# GOLpHAT.net
KiCad netlist of a schematic drawn in EAGLE
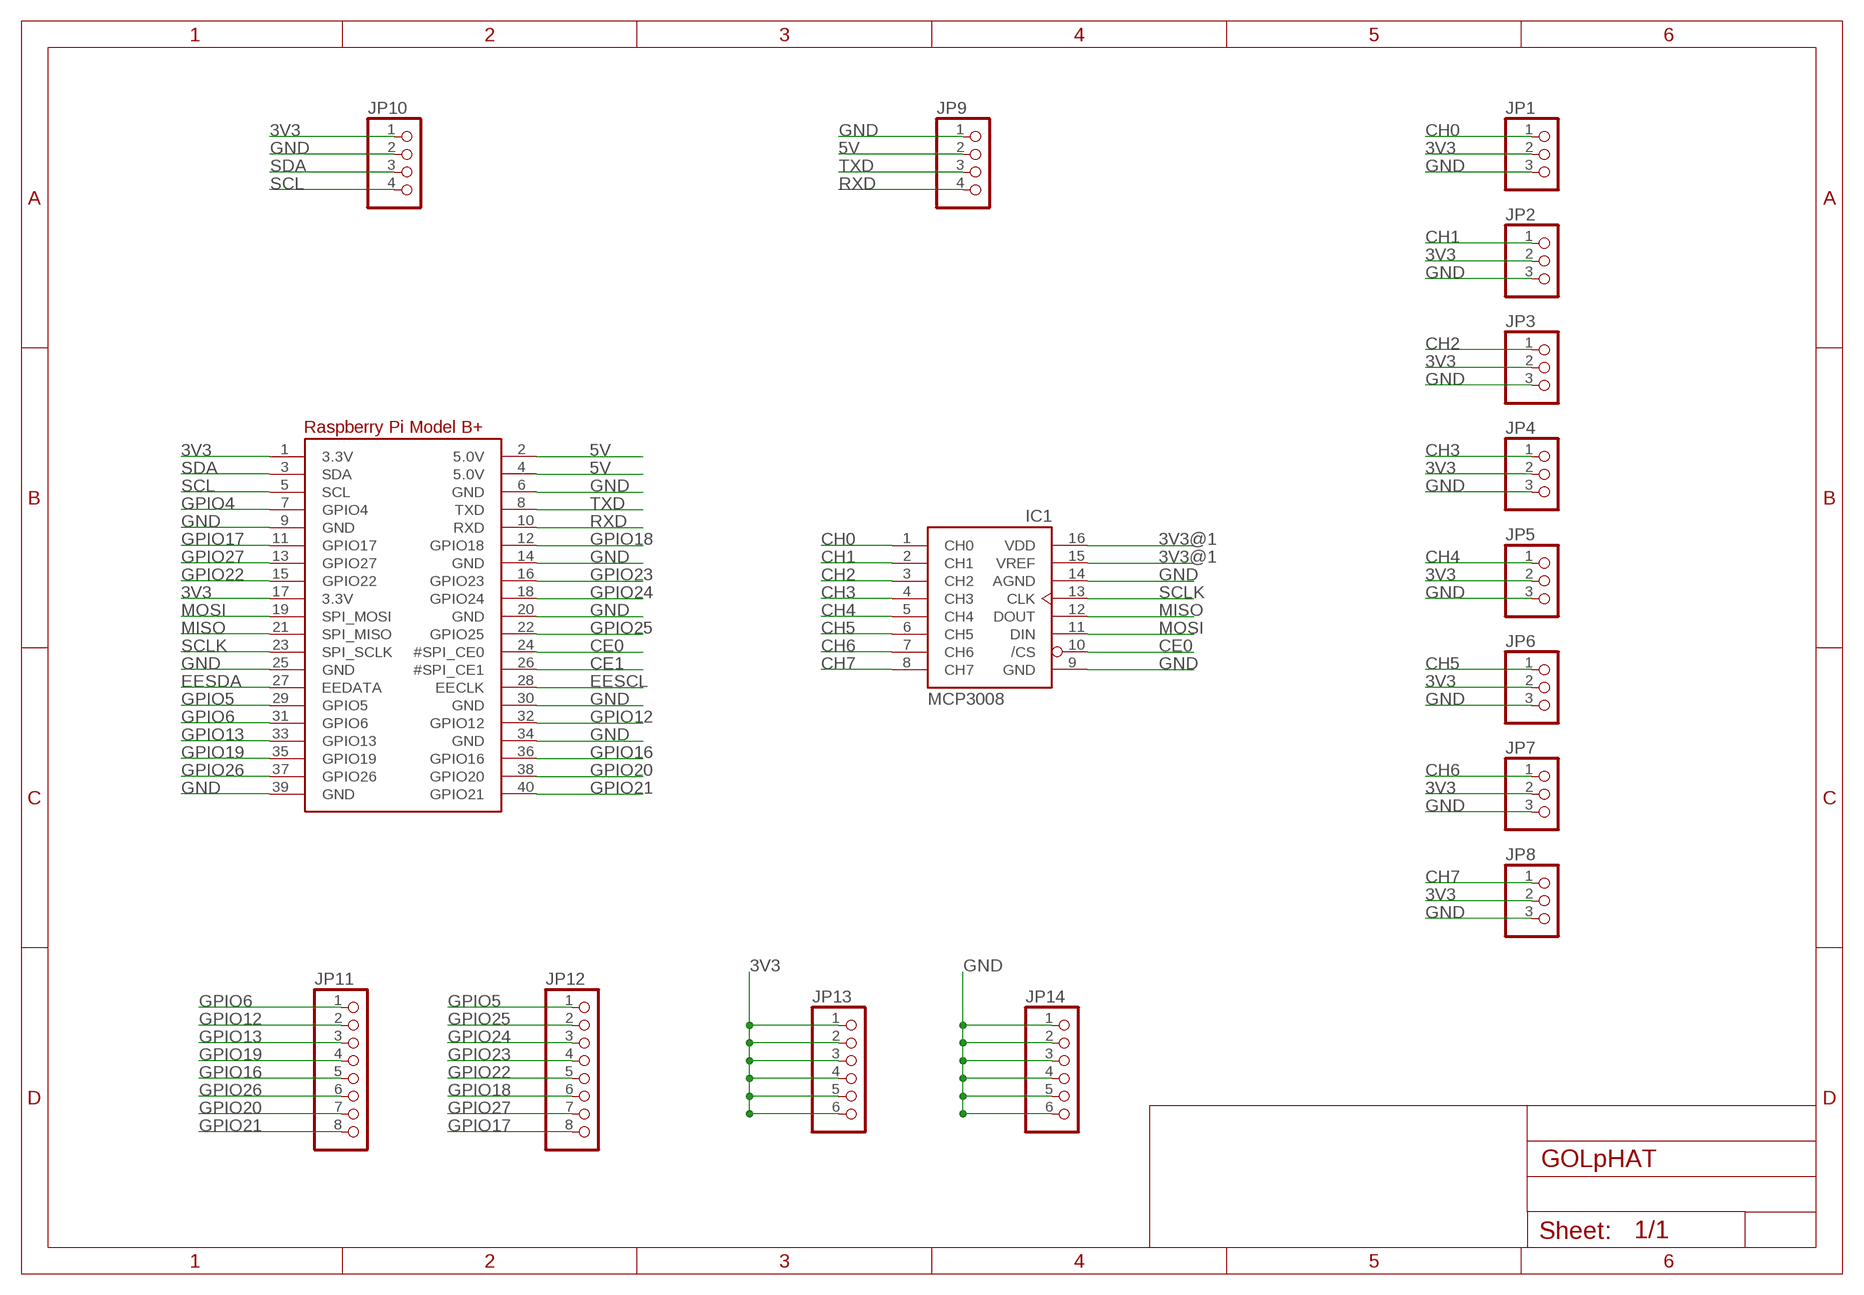
[diagram p0: schematic, sheet 1]

(export (version "E")
  (design (tool "Eeschema 10.0.6"))
  (components
    (comp (ref "IC1")
      (value "MCP3008")
      (footprint "eagle-import:DIL16")
      (libsource (lib "eagle-import") (part "MCP3008"))
    )
    (comp (ref "JP1")
      (value "PINHD-1X3")
      (footprint "eagle-import:1X03")
      (libsource (lib "eagle-import") (part "PINHD-1X3"))
    )
    (comp (ref "JP2")
      (value "PINHD-1X3")
      (footprint "eagle-import:1X03")
      (libsource (lib "eagle-import") (part "PINHD-1X3"))
    )
    (comp (ref "JP3")
      (value "PINHD-1X3")
      (footprint "eagle-import:1X03")
      (libsource (lib "eagle-import") (part "PINHD-1X3"))
    )
    (comp (ref "JP4")
      (value "PINHD-1X3")
      (footprint "eagle-import:1X03")
      (libsource (lib "eagle-import") (part "PINHD-1X3"))
    )
    (comp (ref "JP5")
      (value "PINHD-1X3")
      (footprint "eagle-import:1X03")
      (libsource (lib "eagle-import") (part "PINHD-1X3"))
    )
    (comp (ref "JP6")
      (value "PINHD-1X3")
      (footprint "eagle-import:1X03")
      (libsource (lib "eagle-import") (part "PINHD-1X3"))
    )
    (comp (ref "JP7")
      (value "PINHD-1X3")
      (footprint "eagle-import:1X03")
      (libsource (lib "eagle-import") (part "PINHD-1X3"))
    )
    (comp (ref "JP8")
      (value "PINHD-1X3")
      (footprint "eagle-import:1X03")
      (libsource (lib "eagle-import") (part "PINHD-1X3"))
    )
    (comp (ref "JP9")
      (value "PINHD-1X4")
      (footprint "eagle-import:1X04")
      (libsource (lib "eagle-import") (part "PINHD-1X4"))
    )
    (comp (ref "JP10")
      (value "PINHD-1X4")
      (footprint "eagle-import:1X04")
      (libsource (lib "eagle-import") (part "PINHD-1X4"))
    )
    (comp (ref "JP11")
      (value "PINHD-1X8CLEANBIG")
      (footprint "eagle-import:1X08-CLEANBIG")
      (libsource (lib "eagle-import") (part "PINHD-1X8CLEANBIG"))
    )
    (comp (ref "JP12")
      (value "PINHD-1X8CLEANBIG")
      (footprint "eagle-import:1X08-CLEANBIG")
      (libsource (lib "eagle-import") (part "PINHD-1X8CLEANBIG"))
    )
    (comp (ref "JP13")
      (value "PINHD-1X6CB")
      (footprint "eagle-import:1X06-CLEANBIG")
      (libsource (lib "eagle-import") (part "PINHD-1X6CB"))
    )
    (comp (ref "JP14")
      (value "PINHD-1X6CB")
      (footprint "eagle-import:1X06-CLEANBIG")
      (libsource (lib "eagle-import") (part "PINHD-1X6CB"))
    )
    (comp (ref "RPI1")
      (value "RASPBERRYPI_BPLUS_PHAT")
      (footprint "eagle-import:PI_BONNET")
      (libsource (lib "eagle-import") (part "RASPBERRYPI_BPLUS_PHAT"))
    )
  )
  (nets
    (net (code "1") (name "/3V3") (class "Default")
      (node (ref "JP1") (pin "2") (pinfunction "2_2") (pintype "passive"))
      (node (ref "JP10") (pin "1") (pinfunction "1_1") (pintype "passive"))
      (node (ref "JP13") (pin "1") (pinfunction "1_1") (pintype "passive"))
      (node (ref "JP13") (pin "2") (pinfunction "2_2") (pintype "passive"))
      (node (ref "JP13") (pin "3") (pinfunction "3_3") (pintype "passive"))
      (node (ref "JP13") (pin "4") (pinfunction "4_4") (pintype "passive"))
      (node (ref "JP13") (pin "5") (pinfunction "5_5") (pintype "passive"))
      (node (ref "JP13") (pin "6") (pinfunction "6_6") (pintype "passive"))
      (node (ref "JP2") (pin "2") (pinfunction "2_2") (pintype "passive"))
      (node (ref "JP3") (pin "2") (pinfunction "2_2") (pintype "passive"))
      (node (ref "JP4") (pin "2") (pinfunction "2_2") (pintype "passive"))
      (node (ref "JP5") (pin "2") (pinfunction "2_2") (pintype "passive"))
      (node (ref "JP6") (pin "2") (pinfunction "2_2") (pintype "passive"))
      (node (ref "JP7") (pin "2") (pinfunction "2_2") (pintype "passive"))
      (node (ref "JP8") (pin "2") (pinfunction "2_2") (pintype "passive"))
      (node (ref "RPI1") (pin "1") (pinfunction "3.3V_1") (pintype "power_in"))
      (node (ref "RPI1") (pin "17") (pinfunction "3.3V_17") (pintype "power_in"))
    )
    (net (code "2") (name "/3V3@1") (class "Default")
      (node (ref "IC1") (pin "15") (pinfunction "VREF_15") (pintype "input"))
      (node (ref "IC1") (pin "16") (pinfunction "VDD_16") (pintype "power_in"))
    )
    (net (code "3") (name "/5V") (class "Default")
      (node (ref "JP9") (pin "2") (pinfunction "2_2") (pintype "passive"))
      (node (ref "RPI1") (pin "2") (pinfunction "5.0V_2") (pintype "power_in"))
      (node (ref "RPI1") (pin "4") (pinfunction "5.0V_4") (pintype "power_in"))
    )
    (net (code "4") (name "/CE0") (class "Default")
      (node (ref "IC1") (pin "10") (pinfunction "/CS_10") (pintype "input"))
      (node (ref "RPI1") (pin "24") (pinfunction "#SPI_CE0_24") (pintype "bidirectional"))
    )
    (net (code "5") (name "/CE1") (class "Default")
      (node (ref "RPI1") (pin "26") (pinfunction "#SPI_CE1_26") (pintype "bidirectional"))
    )
    (net (code "6") (name "/CH0") (class "Default")
      (node (ref "IC1") (pin "1") (pinfunction "CH0_1") (pintype "input"))
      (node (ref "JP1") (pin "1") (pinfunction "1_1") (pintype "passive"))
    )
    (net (code "7") (name "/CH1") (class "Default")
      (node (ref "IC1") (pin "2") (pinfunction "CH1_2") (pintype "input"))
      (node (ref "JP2") (pin "1") (pinfunction "1_1") (pintype "passive"))
    )
    (net (code "8") (name "/CH2") (class "Default")
      (node (ref "IC1") (pin "3") (pinfunction "CH2_3") (pintype "input"))
      (node (ref "JP3") (pin "1") (pinfunction "1_1") (pintype "passive"))
    )
    (net (code "9") (name "/CH3") (class "Default")
      (node (ref "IC1") (pin "4") (pinfunction "CH3_4") (pintype "input"))
      (node (ref "JP4") (pin "1") (pinfunction "1_1") (pintype "passive"))
    )
    (net (code "10") (name "/CH4") (class "Default")
      (node (ref "IC1") (pin "5") (pinfunction "CH4_5") (pintype "input"))
      (node (ref "JP5") (pin "1") (pinfunction "1_1") (pintype "passive"))
    )
    (net (code "11") (name "/CH5") (class "Default")
      (node (ref "IC1") (pin "6") (pinfunction "CH5_6") (pintype "input"))
      (node (ref "JP6") (pin "1") (pinfunction "1_1") (pintype "passive"))
    )
    (net (code "12") (name "/CH6") (class "Default")
      (node (ref "IC1") (pin "7") (pinfunction "CH6_7") (pintype "input"))
      (node (ref "JP7") (pin "1") (pinfunction "1_1") (pintype "passive"))
    )
    (net (code "13") (name "/CH7") (class "Default")
      (node (ref "IC1") (pin "8") (pinfunction "CH7_8") (pintype "input"))
      (node (ref "JP8") (pin "1") (pinfunction "1_1") (pintype "passive"))
    )
    (net (code "14") (name "/EESCL") (class "Default")
      (node (ref "RPI1") (pin "28") (pinfunction "EECLK_28") (pintype "bidirectional"))
    )
    (net (code "15") (name "/EESDA") (class "Default")
      (node (ref "RPI1") (pin "27") (pinfunction "EEDATA_27") (pintype "bidirectional"))
    )
    (net (code "16") (name "/GND") (class "Default")
      (node (ref "IC1") (pin "14") (pinfunction "AGND_14") (pintype "power_in"))
      (node (ref "IC1") (pin "9") (pinfunction "GND_9") (pintype "power_in"))
      (node (ref "JP1") (pin "3") (pinfunction "3_3") (pintype "passive"))
      (node (ref "JP10") (pin "2") (pinfunction "2_2") (pintype "passive"))
      (node (ref "JP14") (pin "1") (pinfunction "1_1") (pintype "passive"))
      (node (ref "JP14") (pin "2") (pinfunction "2_2") (pintype "passive"))
      (node (ref "JP14") (pin "3") (pinfunction "3_3") (pintype "passive"))
      (node (ref "JP14") (pin "4") (pinfunction "4_4") (pintype "passive"))
      (node (ref "JP14") (pin "5") (pinfunction "5_5") (pintype "passive"))
      (node (ref "JP14") (pin "6") (pinfunction "6_6") (pintype "passive"))
      (node (ref "JP2") (pin "3") (pinfunction "3_3") (pintype "passive"))
      (node (ref "JP3") (pin "3") (pinfunction "3_3") (pintype "passive"))
      (node (ref "JP4") (pin "3") (pinfunction "3_3") (pintype "passive"))
      (node (ref "JP5") (pin "3") (pinfunction "3_3") (pintype "passive"))
      (node (ref "JP6") (pin "3") (pinfunction "3_3") (pintype "passive"))
      (node (ref "JP7") (pin "3") (pinfunction "3_3") (pintype "passive"))
      (node (ref "JP8") (pin "3") (pinfunction "3_3") (pintype "passive"))
      (node (ref "JP9") (pin "1") (pinfunction "1_1") (pintype "passive"))
      (node (ref "RPI1") (pin "14") (pinfunction "GND_14") (pintype "power_in"))
      (node (ref "RPI1") (pin "20") (pinfunction "GND_20") (pintype "power_in"))
      (node (ref "RPI1") (pin "25") (pinfunction "GND_25") (pintype "power_in"))
      (node (ref "RPI1") (pin "30") (pinfunction "GND_30") (pintype "power_in"))
      (node (ref "RPI1") (pin "34") (pinfunction "GND_34") (pintype "power_in"))
      (node (ref "RPI1") (pin "39") (pinfunction "GND_39") (pintype "power_in"))
      (node (ref "RPI1") (pin "6") (pinfunction "GND_6") (pintype "power_in"))
      (node (ref "RPI1") (pin "9") (pinfunction "GND_9") (pintype "power_in"))
    )
    (net (code "17") (name "/GPIO4") (class "Default")
      (node (ref "RPI1") (pin "7") (pinfunction "GPIO4_7") (pintype "bidirectional"))
    )
    (net (code "18") (name "/GPIO5") (class "Default")
      (node (ref "JP12") (pin "1") (pinfunction "1_1") (pintype "passive"))
      (node (ref "RPI1") (pin "29") (pinfunction "GPIO5_29") (pintype "bidirectional"))
    )
    (net (code "19") (name "/GPIO6") (class "Default")
      (node (ref "JP11") (pin "1") (pinfunction "1_1") (pintype "passive"))
      (node (ref "RPI1") (pin "31") (pinfunction "GPIO6_31") (pintype "bidirectional"))
    )
    (net (code "20") (name "/GPIO12") (class "Default")
      (node (ref "JP11") (pin "2") (pinfunction "2_2") (pintype "passive"))
      (node (ref "RPI1") (pin "32") (pinfunction "GPIO12_32") (pintype "bidirectional"))
    )
    (net (code "21") (name "/GPIO13") (class "Default")
      (node (ref "JP11") (pin "3") (pinfunction "3_3") (pintype "passive"))
      (node (ref "RPI1") (pin "33") (pinfunction "GPIO13_33") (pintype "bidirectional"))
    )
    (net (code "22") (name "/GPIO16") (class "Default")
      (node (ref "JP11") (pin "5") (pinfunction "5_5") (pintype "passive"))
      (node (ref "RPI1") (pin "36") (pinfunction "GPIO16_36") (pintype "bidirectional"))
    )
    (net (code "23") (name "/GPIO17") (class "Default")
      (node (ref "JP12") (pin "8") (pinfunction "8_8") (pintype "passive"))
      (node (ref "RPI1") (pin "11") (pinfunction "GPIO17_11") (pintype "bidirectional"))
    )
    (net (code "24") (name "/GPIO18") (class "Default")
      (node (ref "JP12") (pin "6") (pinfunction "6_6") (pintype "passive"))
      (node (ref "RPI1") (pin "12") (pinfunction "GPIO18_12") (pintype "bidirectional"))
    )
    (net (code "25") (name "/GPIO19") (class "Default")
      (node (ref "JP11") (pin "4") (pinfunction "4_4") (pintype "passive"))
      (node (ref "RPI1") (pin "35") (pinfunction "GPIO19_35") (pintype "bidirectional"))
    )
    (net (code "26") (name "/GPIO20") (class "Default")
      (node (ref "JP11") (pin "7") (pinfunction "7_7") (pintype "passive"))
      (node (ref "RPI1") (pin "38") (pinfunction "GPIO20_38") (pintype "bidirectional"))
    )
    (net (code "27") (name "/GPIO21") (class "Default")
      (node (ref "JP11") (pin "8") (pinfunction "8_8") (pintype "passive"))
      (node (ref "RPI1") (pin "40") (pinfunction "GPIO21_40") (pintype "bidirectional"))
    )
    (net (code "28") (name "/GPIO22") (class "Default")
      (node (ref "JP12") (pin "5") (pinfunction "5_5") (pintype "passive"))
      (node (ref "RPI1") (pin "15") (pinfunction "GPIO22_15") (pintype "bidirectional"))
    )
    (net (code "29") (name "/GPIO23") (class "Default")
      (node (ref "JP12") (pin "4") (pinfunction "4_4") (pintype "passive"))
      (node (ref "RPI1") (pin "16") (pinfunction "GPIO23_16") (pintype "bidirectional"))
    )
    (net (code "30") (name "/GPIO24") (class "Default")
      (node (ref "JP12") (pin "3") (pinfunction "3_3") (pintype "passive"))
      (node (ref "RPI1") (pin "18") (pinfunction "GPIO24_18") (pintype "bidirectional"))
    )
    (net (code "31") (name "/GPIO25") (class "Default")
      (node (ref "JP12") (pin "2") (pinfunction "2_2") (pintype "passive"))
      (node (ref "RPI1") (pin "22") (pinfunction "GPIO25_22") (pintype "bidirectional"))
    )
    (net (code "32") (name "/GPIO26") (class "Default")
      (node (ref "JP11") (pin "6") (pinfunction "6_6") (pintype "passive"))
      (node (ref "RPI1") (pin "37") (pinfunction "GPIO26_37") (pintype "bidirectional"))
    )
    (net (code "33") (name "/GPIO27") (class "Default")
      (node (ref "JP12") (pin "7") (pinfunction "7_7") (pintype "passive"))
      (node (ref "RPI1") (pin "13") (pinfunction "GPIO27_13") (pintype "bidirectional"))
    )
    (net (code "34") (name "/MISO") (class "Default")
      (node (ref "IC1") (pin "12") (pinfunction "DOUT_12") (pintype "output"))
      (node (ref "RPI1") (pin "21") (pinfunction "SPI_MISO_21") (pintype "bidirectional"))
    )
    (net (code "35") (name "/MOSI") (class "Default")
      (node (ref "IC1") (pin "11") (pinfunction "DIN_11") (pintype "input"))
      (node (ref "RPI1") (pin "19") (pinfunction "SPI_MOSI_19") (pintype "bidirectional"))
    )
    (net (code "36") (name "/RXD") (class "Default")
      (node (ref "JP9") (pin "4") (pinfunction "4_4") (pintype "passive"))
      (node (ref "RPI1") (pin "10") (pinfunction "RXD_10") (pintype "bidirectional"))
    )
    (net (code "37") (name "/SCL") (class "Default")
      (node (ref "JP10") (pin "4") (pinfunction "4_4") (pintype "passive"))
      (node (ref "RPI1") (pin "5") (pinfunction "SCL_5") (pintype "bidirectional"))
    )
    (net (code "38") (name "/SCLK") (class "Default")
      (node (ref "IC1") (pin "13") (pinfunction "CLK_13") (pintype "input"))
      (node (ref "RPI1") (pin "23") (pinfunction "SPI_SCLK_23") (pintype "bidirectional"))
    )
    (net (code "39") (name "/SDA") (class "Default")
      (node (ref "JP10") (pin "3") (pinfunction "3_3") (pintype "passive"))
      (node (ref "RPI1") (pin "3") (pinfunction "SDA_3") (pintype "bidirectional"))
    )
    (net (code "40") (name "/TXD") (class "Default")
      (node (ref "JP9") (pin "3") (pinfunction "3_3") (pintype "passive"))
      (node (ref "RPI1") (pin "8") (pinfunction "TXD_8") (pintype "bidirectional"))
    )
  )
)
